# PA.net
KiCad netlist of a schematic drawn in Altium Designer
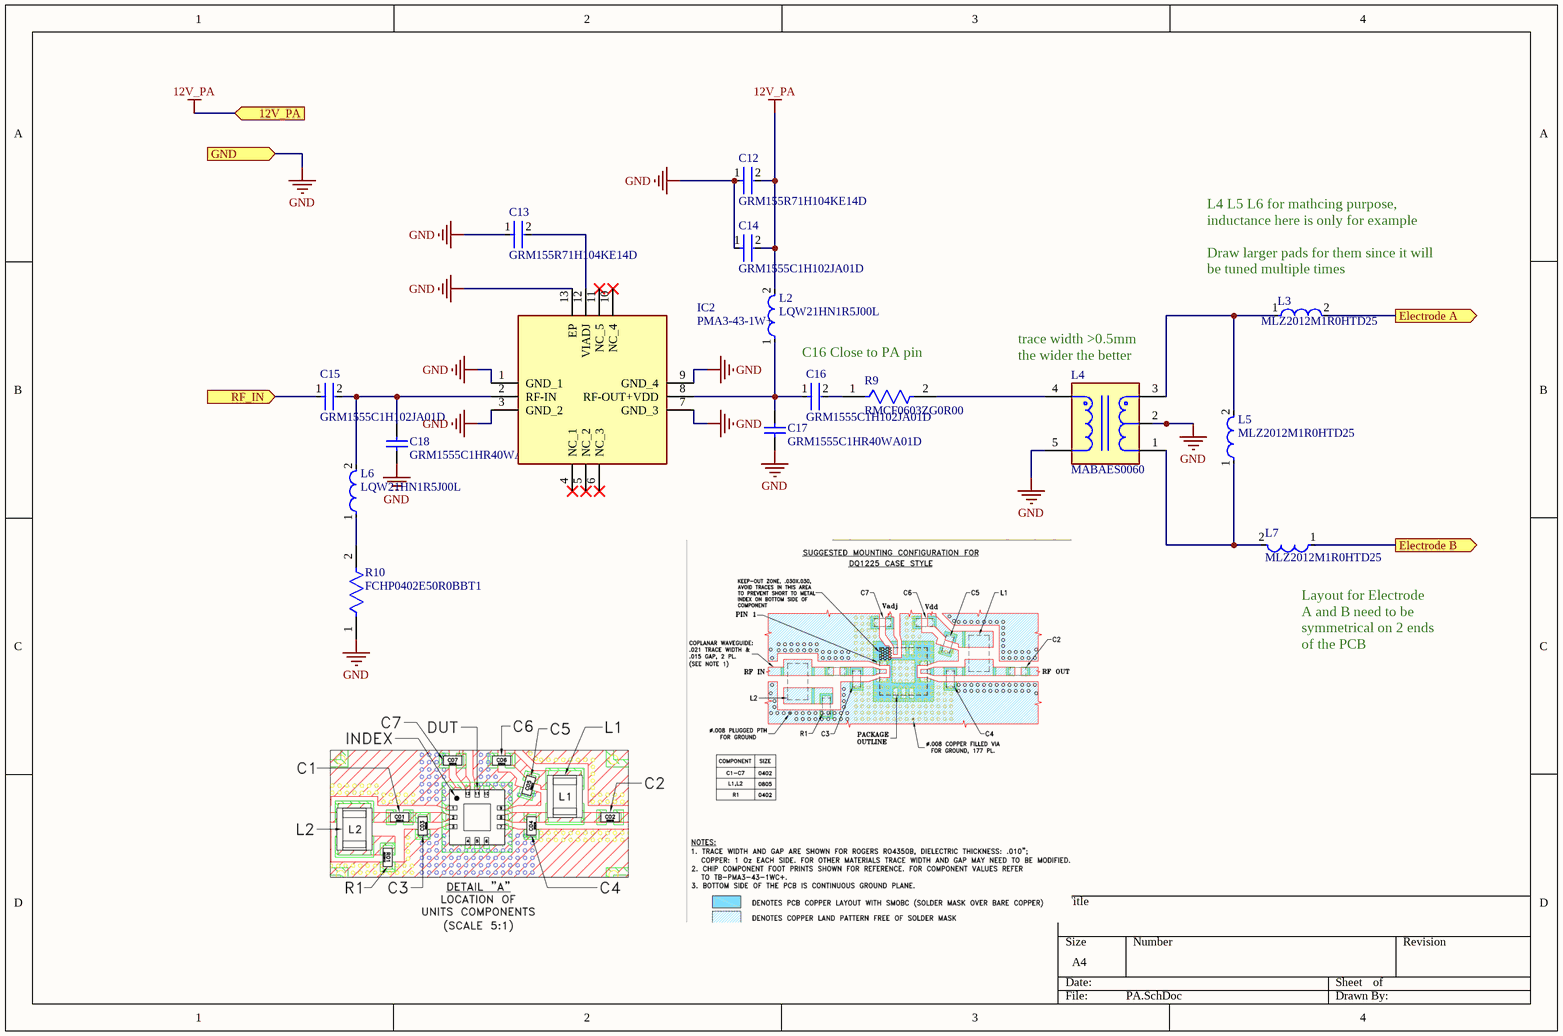
[diagram p0: PA.SchDoc]

(export (version "E")
  (design (tool "Eeschema 10.0.6"))
  (components
    (comp (ref "C12")
      (value "GRM155R71H104KE14D")
      (footprint "FP-GRM155-0_05-IPC_B")
      (description "Chip Multilayer Ceramic Capacitors for General Purpose, 0402, 0.10uF, X7R, 15%, 10%, 50V")
      (fields (field (name "VOLTAGE") "50V") (field (name "TOLERANCE") "10%"))
      (libsource (lib "Altium Content Vault") (part "02cd4be3c70576c341d710602a673aa"))
    )
    (comp (ref "C13")
      (value "GRM155R71H104KE14D")
      (footprint "FP-GRM155-0_05-IPC_B")
      (description "Chip Multilayer Ceramic Capacitors for General Purpose, 0402, 0.10uF, X7R, 15%, 10%, 50V")
      (fields (field (name "VOLTAGE") "50V") (field (name "TOLERANCE") "10%"))
      (libsource (lib "Altium Content Vault") (part "02cd4be3c70576c341d710602a673aa"))
    )
    (comp (ref "C14")
      (value "GRM1555C1H102JA01D")
      (footprint "FP-GRM155-0_05-IPC_B")
      (description "Chip Multilayer Ceramic Capacitors for General Purpose, 0402, 1000pF, C0G, 30ppm/°C, 5%, 50V")
      (fields (field (name "TOLERANCE") "5%") (field (name "VOLTAGE") "50V"))
      (libsource (lib "Altium Content Vault") (part "02cd4be3c70576c341d710602a673aa"))
    )
    (comp (ref "C15")
      (value "GRM1555C1H102JA01D")
      (footprint "FP-GRM155-0_05-IPC_B")
      (description "Chip Multilayer Ceramic Capacitors for General Purpose, 0402, 1000pF, C0G, 30ppm/°C, 5%, 50V")
      (fields (field (name "TOLERANCE") "5%") (field (name "VOLTAGE") "50V"))
      (libsource (lib "Altium Content Vault") (part "02cd4be3c70576c341d710602a673aa"))
    )
    (comp (ref "C16")
      (value "GRM1555C1H102JA01D")
      (footprint "FP-GRM155-0_05-IPC_B")
      (description "Chip Multilayer Ceramic Capacitors for General Purpose, 0402, 1000pF, C0G, 30ppm/°C, 5%, 50V")
      (fields (field (name "TOLERANCE") "5%") (field (name "VOLTAGE") "50V"))
      (libsource (lib "Altium Content Vault") (part "02cd4be3c70576c341d710602a673aa"))
    )
    (comp (ref "C17")
      (value "GRM1555C1HR40WA01D")
      (footprint "CAPC1005X55X25LL05T10")
      (fields (field (name "MANUFACTURER") "Murata"))
      (libsource (lib "Altium Content Vault") (part "CAP"))
    )
    (comp (ref "C18")
      (value "GRM1555C1HR40WA01D")
      (footprint "CAPC1005X55X25LL05T10")
      (fields (field (name "MANUFACTURER") "Murata"))
      (libsource (lib "Altium Content Vault") (part "CAP"))
    )
    (comp (ref "IC2")
      (value "PMA3-43-1W+")
      (footprint "QFN51P300X300X89-13N")
      (description "Integrated Circuit")
      (libsource (lib "SamacSys") (part "PMA3-43-1W+"))
    )
    (comp (ref "L2")
      (value "LQW21HN1R5J00L")
      (footprint "FP-LQW21HN_00-MFG")
      (description "Wire Wound Ferrite type RF Inuctor 1.5uH ±5% 85mA 5.33Ω 0805 (2012)")
      (fields (field (name "TOLERANCE") "5%"))
      (libsource (lib "Altium Content Vault") (part "725321dda6339637d4d059423bc1c3c"))
    )
    (comp (ref "L3")
      (value "MLZ2012M1R0HTD25")
      (footprint "FP-MLZ2012-1_25-IPC_C")
      (description "Shielded Multilayer Inductor 1uH ±20% 800mA 130mΩ AEC-Q200 SMD 0805")
      (fields (field (name "TOLERANCE") "20%"))
      (libsource (lib "Altium Content Vault") (part "725321dda6339637d4d059423bc1c3c"))
    )
    (comp (ref "L4")
      (value "MABAES0060")
      (footprint "FP-MABAES0060-MFG")
      (description "BALUN 300KHZ-200MHZ 1:1 6SMD")
      (libsource (lib "Altium Content Vault") (part "a416973d4767a0660ebfda87df8877f"))
    )
    (comp (ref "L5")
      (value "MLZ2012M1R0HTD25")
      (footprint "FP-MLZ2012-1_25-IPC_C")
      (description "Shielded Multilayer Inductor 1uH ±20% 800mA 130mΩ AEC-Q200 SMD 0805")
      (fields (field (name "TOLERANCE") "20%"))
      (libsource (lib "Altium Content Vault") (part "725321dda6339637d4d059423bc1c3c"))
    )
    (comp (ref "L6")
      (value "LQW21HN1R5J00L")
      (footprint "FP-LQW21HN_00-MFG")
      (description "Wire Wound Ferrite type RF Inuctor 1.5uH ±5% 85mA 5.33Ω 0805 (2012)")
      (fields (field (name "TOLERANCE") "5%"))
      (libsource (lib "Altium Content Vault") (part "725321dda6339637d4d059423bc1c3c"))
    )
    (comp (ref "L7")
      (value "MLZ2012M1R0HTD25")
      (footprint "FP-MLZ2012-1_25-IPC_C")
      (description "Shielded Multilayer Inductor 1uH ±20% 800mA 130mΩ AEC-Q200 SMD 0805")
      (fields (field (name "TOLERANCE") "20%"))
      (libsource (lib "Altium Content Vault") (part "725321dda6339637d4d059423bc1c3c"))
    )
    (comp (ref "R9")
      (value "RMCF0603ZG0R00")
      (footprint "FP-RMCF0603-IPC_B")
      (description "0Ω ±0 0.1W 0603 Thick Film Chip Resistor AEC-Q200 compliant")
      (libsource (lib "Altium Content Vault") (part "1029c3af85768c4190bb7ad29bc67b5"))
    )
    (comp (ref "R10")
      (value "FCHP0402E50R0BBT1")
      (footprint "FP-FC0402-MFG")
      (fields (field (name "TOLERANCE") "0.1%"))
      (libsource (lib "Altium Content Vault") (part "1029c3af85768c4190bb7ad29bc67b5"))
    )
  )
  (nets
    (net (code "1") (name "/Electrode A") (class "Default")
      (node (ref "L3") (pin "2") (pinfunction "2_2") (pintype "passive"))
    )
    (net (code "2") (name "/Electrode B") (class "Default")
      (node (ref "L7") (pin "1") (pinfunction "1_1") (pintype "passive"))
    )
    (net (code "3") (name "/RF_IN") (class "Default")
      (node (ref "C15") (pin "1") (pinfunction "1_1") (pintype "passive"))
    )
    (net (code "4") (name "12V_PA") (class "Default")
      (node (ref "C12") (pin "2") (pinfunction "2_2") (pintype "passive"))
      (node (ref "C14") (pin "2") (pinfunction "2_2") (pintype "passive"))
      (node (ref "L2") (pin "2") (pinfunction "2_2") (pintype "passive"))
    )
    (net (code "5") (name "GND") (class "Default")
      (node (ref "C12") (pin "1") (pinfunction "1_1") (pintype "passive"))
      (node (ref "C13") (pin "1") (pinfunction "1_1") (pintype "passive"))
      (node (ref "C14") (pin "1") (pinfunction "1_1") (pintype "passive"))
      (node (ref "C17") (pin "1") (pinfunction "1_1") (pintype "passive"))
      (node (ref "C18") (pin "1") (pinfunction "1_1") (pintype "passive"))
      (node (ref "IC2") (pin "1") (pinfunction "GND_1_1") (pintype "passive"))
      (node (ref "IC2") (pin "13") (pinfunction "EP_13") (pintype "passive"))
      (node (ref "IC2") (pin "3") (pinfunction "GND_2_3") (pintype "passive"))
      (node (ref "IC2") (pin "7") (pinfunction "GND_3_7") (pintype "passive"))
      (node (ref "IC2") (pin "9") (pinfunction "GND_4_9") (pintype "passive"))
      (node (ref "L4") (pin "2") (pinfunction "Secondary_CT_2") (pintype "passive"))
      (node (ref "L4") (pin "5") (pinfunction "Primary_5") (pintype "passive"))
      (node (ref "R10") (pin "1") (pinfunction "1_1") (pintype "passive"))
    )
    (net (code "6") (name "Net-(C16-Pad2)") (class "Default")
      (node (ref "C16") (pin "2") (pinfunction "2_2") (pintype "passive"))
      (node (ref "R9") (pin "1") (pinfunction "1_1") (pintype "passive"))
    )
    (net (code "7") (name "Net-(IC2-RF-IN)") (class "Default")
      (node (ref "C15") (pin "2") (pinfunction "2_2") (pintype "passive"))
      (node (ref "C18") (pin "2") (pinfunction "2_2") (pintype "passive"))
      (node (ref "IC2") (pin "2") (pinfunction "RF-IN_2") (pintype "passive"))
      (node (ref "L6") (pin "2") (pinfunction "2_2") (pintype "passive"))
    )
    (net (code "8") (name "Net-(IC2-RF-OUT+VDD)") (class "Default")
      (node (ref "C16") (pin "1") (pinfunction "1_1") (pintype "passive"))
      (node (ref "C17") (pin "2") (pinfunction "2_2") (pintype "passive"))
      (node (ref "IC2") (pin "8") (pinfunction "RF-OUT+VDD_8") (pintype "passive"))
      (node (ref "L2") (pin "1") (pinfunction "1_1") (pintype "passive"))
    )
    (net (code "9") (name "Net-(IC2-VIADJ)") (class "Default")
      (node (ref "C13") (pin "2") (pinfunction "2_2") (pintype "passive"))
      (node (ref "IC2") (pin "12") (pinfunction "VIADJ_12") (pintype "passive"))
    )
    (net (code "10") (name "Net-(L4-Primary_dot)") (class "Default")
      (node (ref "L4") (pin "4") (pinfunction "Primary_dot_4") (pintype "passive"))
      (node (ref "R9") (pin "2") (pinfunction "2_2") (pintype "passive"))
    )
    (net (code "11") (name "Net-(L4-Secondary)") (class "Default")
      (node (ref "L4") (pin "1") (pinfunction "Secondary_1") (pintype "passive"))
      (node (ref "L5") (pin "1") (pinfunction "1_1") (pintype "passive"))
      (node (ref "L7") (pin "2") (pinfunction "2_2") (pintype "passive"))
    )
    (net (code "12") (name "Net-(L4-Secondary_Dot)") (class "Default")
      (node (ref "L3") (pin "1") (pinfunction "1_1") (pintype "passive"))
      (node (ref "L4") (pin "3") (pinfunction "Secondary_Dot_3") (pintype "passive"))
      (node (ref "L5") (pin "2") (pinfunction "2_2") (pintype "passive"))
    )
    (net (code "13") (name "Net-(L6-Pad1)") (class "Default")
      (node (ref "L6") (pin "1") (pinfunction "1_1") (pintype "passive"))
      (node (ref "R10") (pin "2") (pinfunction "2_2") (pintype "passive"))
    )
    (net (code "14") (name "unconnected-(IC2-NC_1-Pad4)") (class "Default")
      (node (ref "IC2") (pin "4") (pinfunction "NC_1_4") (pintype "passive+no_connect"))
    )
    (net (code "15") (name "unconnected-(IC2-NC_2-Pad5)") (class "Default")
      (node (ref "IC2") (pin "5") (pinfunction "NC_2_5") (pintype "passive+no_connect"))
    )
    (net (code "16") (name "unconnected-(IC2-NC_3-Pad6)") (class "Default")
      (node (ref "IC2") (pin "6") (pinfunction "NC_3_6") (pintype "passive+no_connect"))
    )
    (net (code "17") (name "unconnected-(IC2-NC_4-Pad10)") (class "Default")
      (node (ref "IC2") (pin "10") (pinfunction "NC_4_10") (pintype "passive+no_connect"))
    )
    (net (code "18") (name "unconnected-(IC2-NC_5-Pad11)") (class "Default")
      (node (ref "IC2") (pin "11") (pinfunction "NC_5_11") (pintype "passive+no_connect"))
    )
  )
)
